# headstage-64-coax-adapter_rev2_0.net
KiCad netlist of a schematic drawn in EAGLE
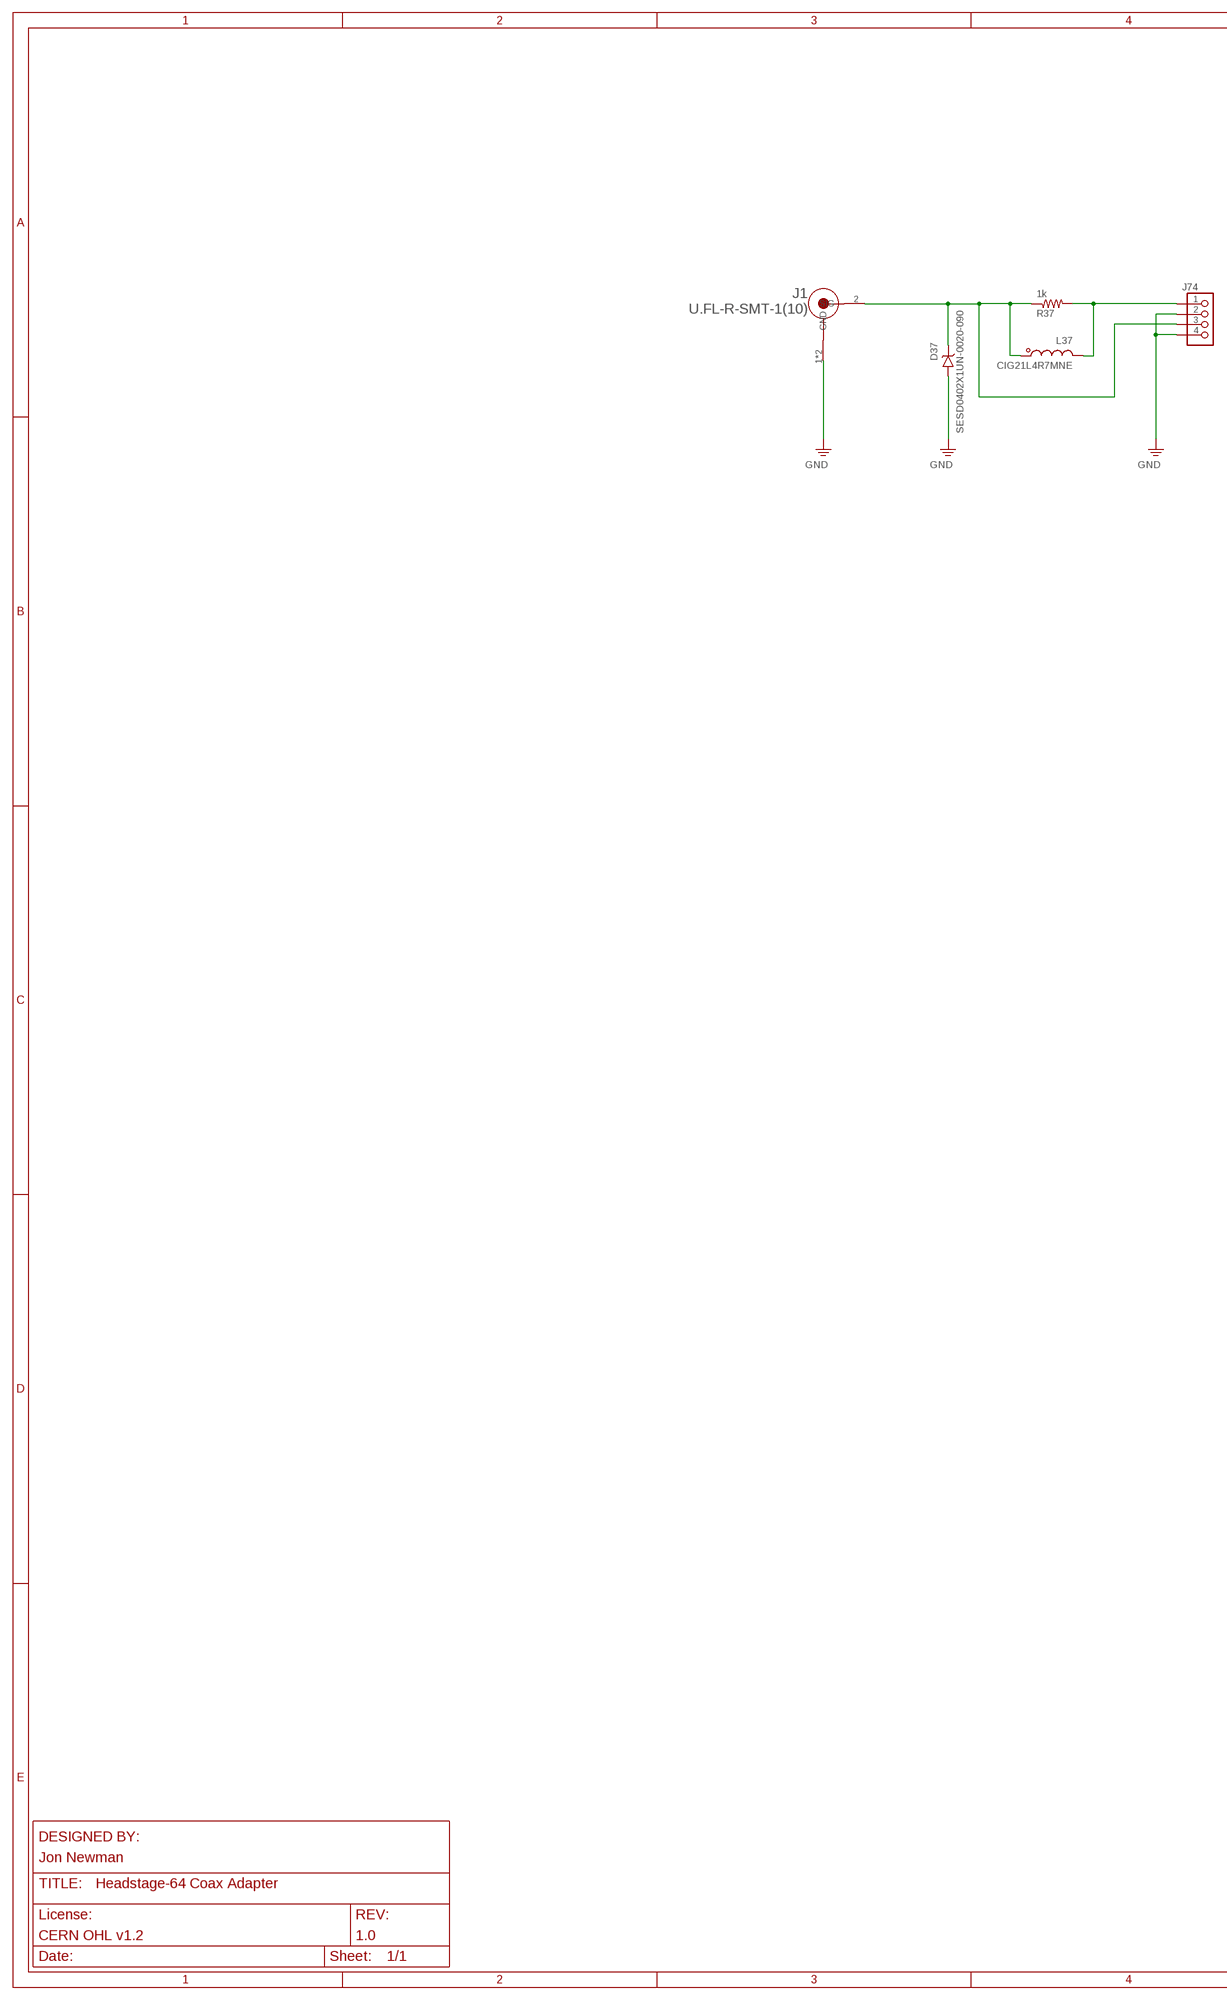
[diagram p0: schematic, sheet 1, part 1 of 2]
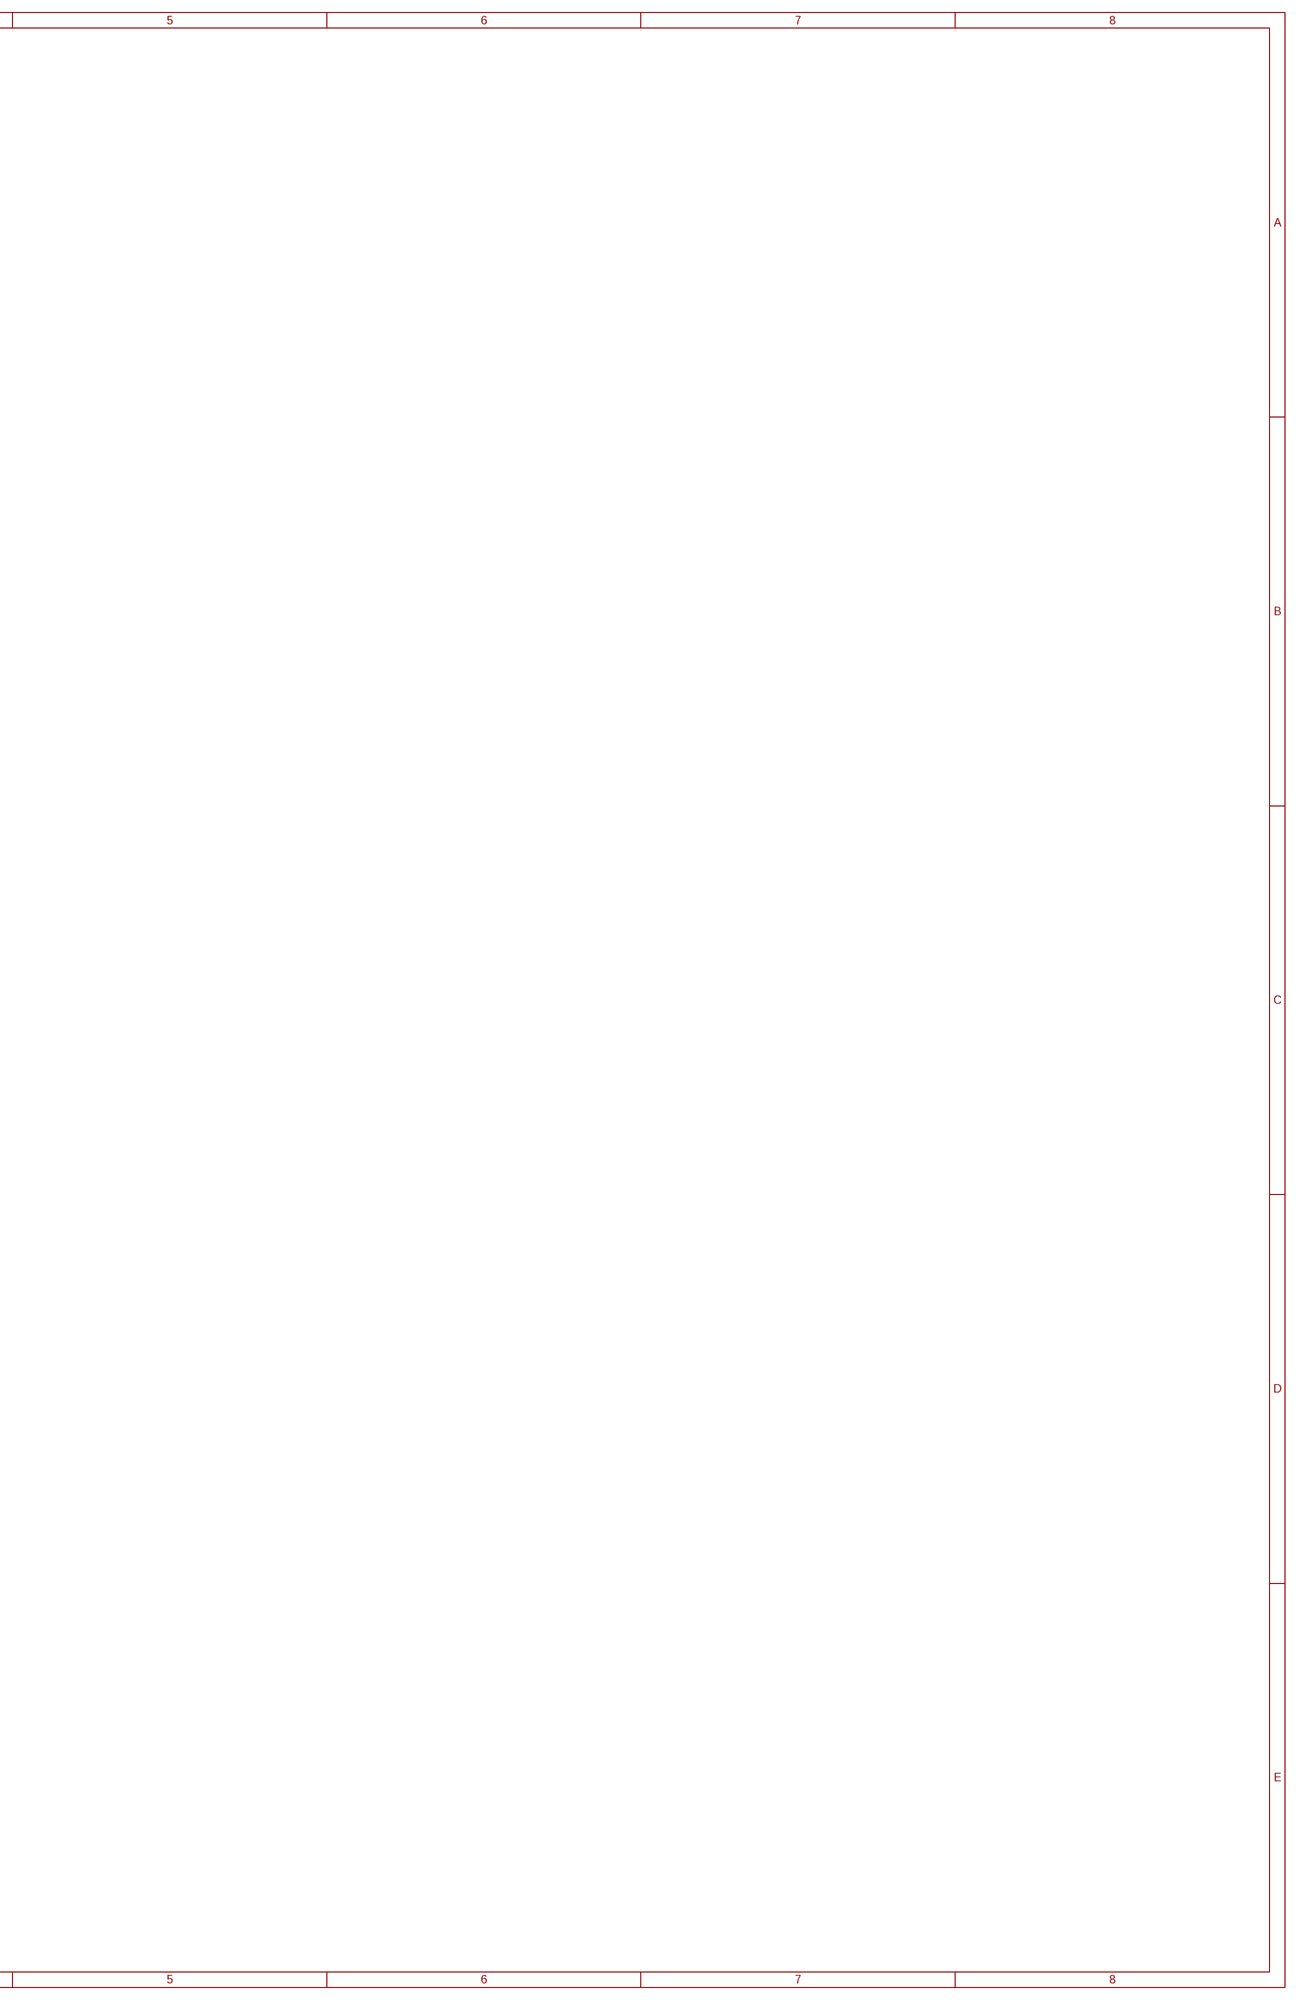
[diagram p1: schematic, sheet 1, part 2 of 2]

(export (version "E")
  (design (tool "Eeschema 10.0.6"))
  (components
    (comp (ref "D37")
      (value "SESD0402X1UN-0020-090")
      (footprint "eagle-import:0402T-DFN")
      (libsource (lib "eagle-import") (part "Z-DIODE_0402T-DFN"))
    )
    (comp (ref "J1")
      (value "U.FL-R-SMT-1(10)")
      (footprint "eagle-import:HRS_U.FL-R-SMT-1(10)")
      (fields (field (name "MF") "Hirose Electric Co Ltd"))
      (libsource (lib "eagle-import") (part "U.FL-R-SMT-1(10)"))
    )
    (comp (ref "J74")
      (value "PINHD-1X4HEADSTAGE64-DAUGHTER-CARD-CASTELLATED")
      (footprint "eagle-import:HEADSTAGE64-DAUGHER-CARD-CASTELLATED")
      (libsource (lib "eagle-import") (part "PINHD-1X4HEADSTAGE64-DAUGHTER-CARD-CASTELLATED"))
    )
    (comp (ref "L37")
      (value "CIG21L4R7MNE")
      (footprint "eagle-import:0805T")
      (libsource (lib "eagle-import") (part "L_0805T"))
    )
    (comp (ref "R37")
      (value "1k")
      (footprint "eagle-import:0201T")
      (libsource (lib "eagle-import") (part "R_0201T"))
    )
  )
  (nets
    (net (code "1") (name "GND") (class "Default")
      (node (ref "D37") (pin "A") (pinfunction "A_A") (pintype "passive"))
      (node (ref "J1") (pin "1") (pinfunction "GND_1") (pintype "passive"))
      (node (ref "J1") (pin "3") (pinfunction "GND_3") (pintype "passive"))
      (node (ref "J74") (pin "2") (pinfunction "2_2") (pintype "passive"))
      (node (ref "J74") (pin "4") (pinfunction "4_4") (pintype "passive"))
    )
    (net (code "2") (name "Net-(J1-SIG)") (class "Default")
      (node (ref "D37") (pin "C") (pinfunction "C_C") (pintype "passive"))
      (node (ref "J1") (pin "2") (pinfunction "SIG_2") (pintype "passive"))
      (node (ref "J74") (pin "3") (pinfunction "3_3") (pintype "passive"))
      (node (ref "L37") (pin "1") (pinfunction "1_1") (pintype "passive"))
      (node (ref "R37") (pin "1") (pinfunction "1_1") (pintype "passive"))
    )
    (net (code "3") (name "Net-(J74-Pad1)") (class "Default")
      (node (ref "J74") (pin "1") (pinfunction "1_1") (pintype "passive"))
      (node (ref "L37") (pin "2") (pinfunction "2_2") (pintype "passive"))
      (node (ref "R37") (pin "2") (pinfunction "2_2") (pintype "passive"))
    )
  )
)
